# M66v2SCH.net
KiCad netlist of a schematic drawn in Altium Designer
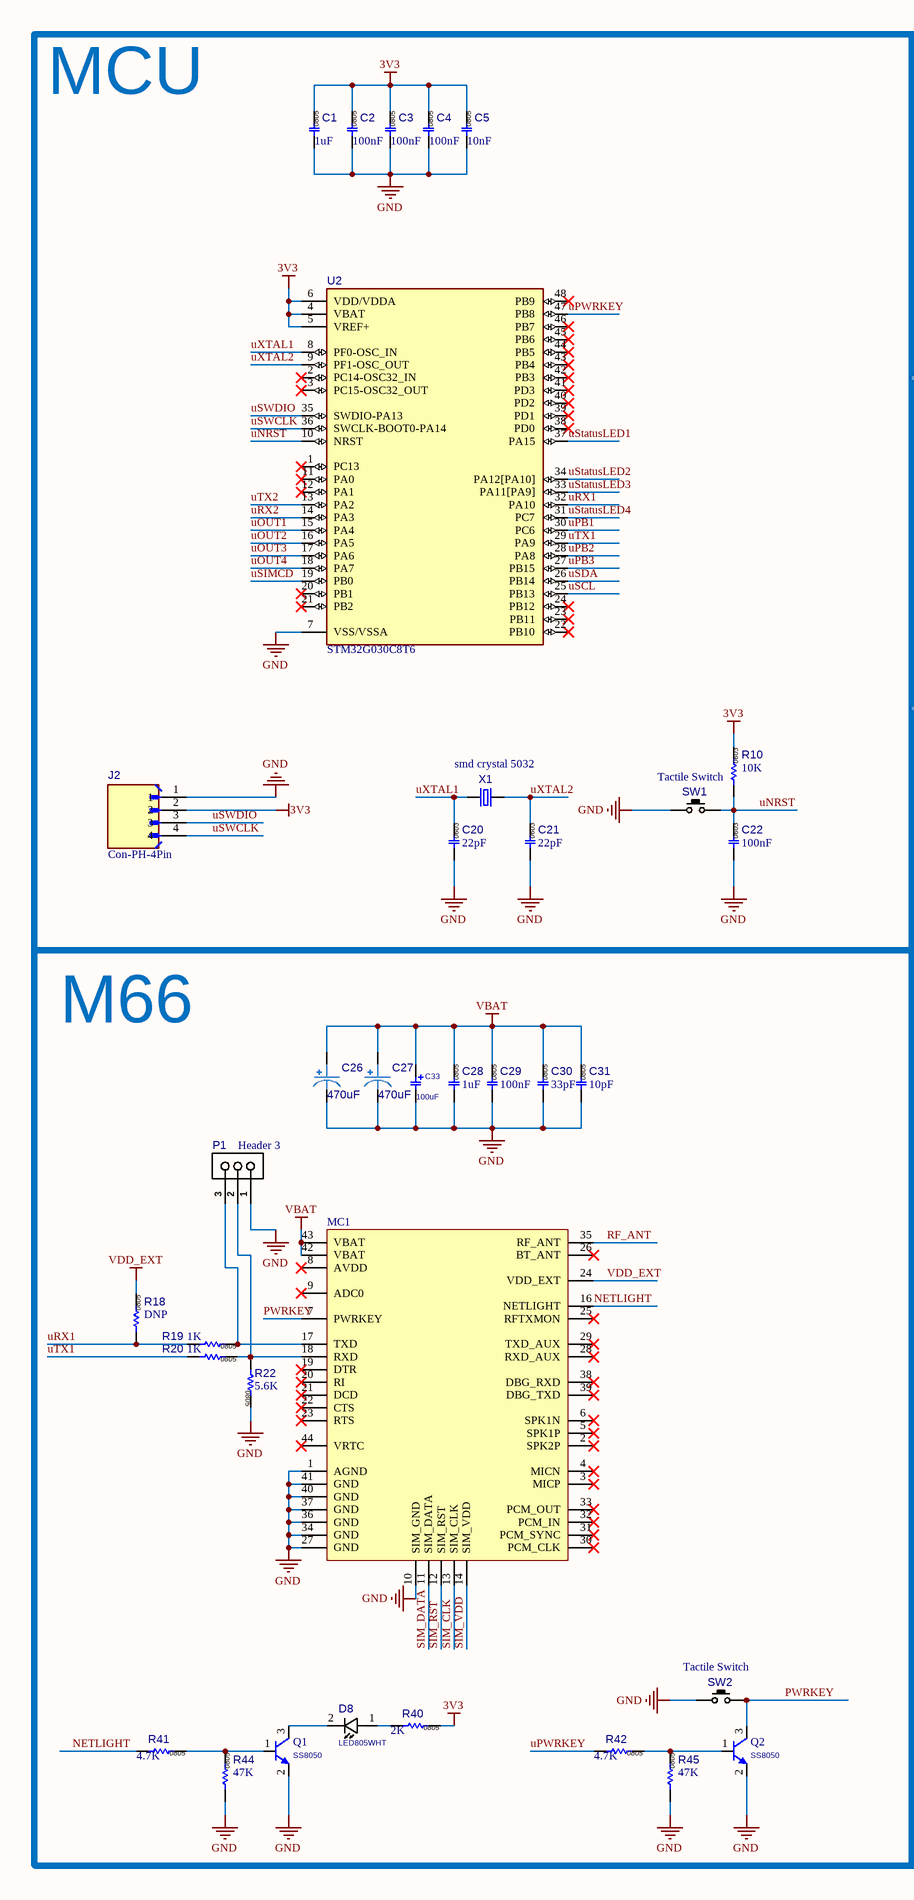
[diagram p0: M66v2SCH.SchDoc, left]
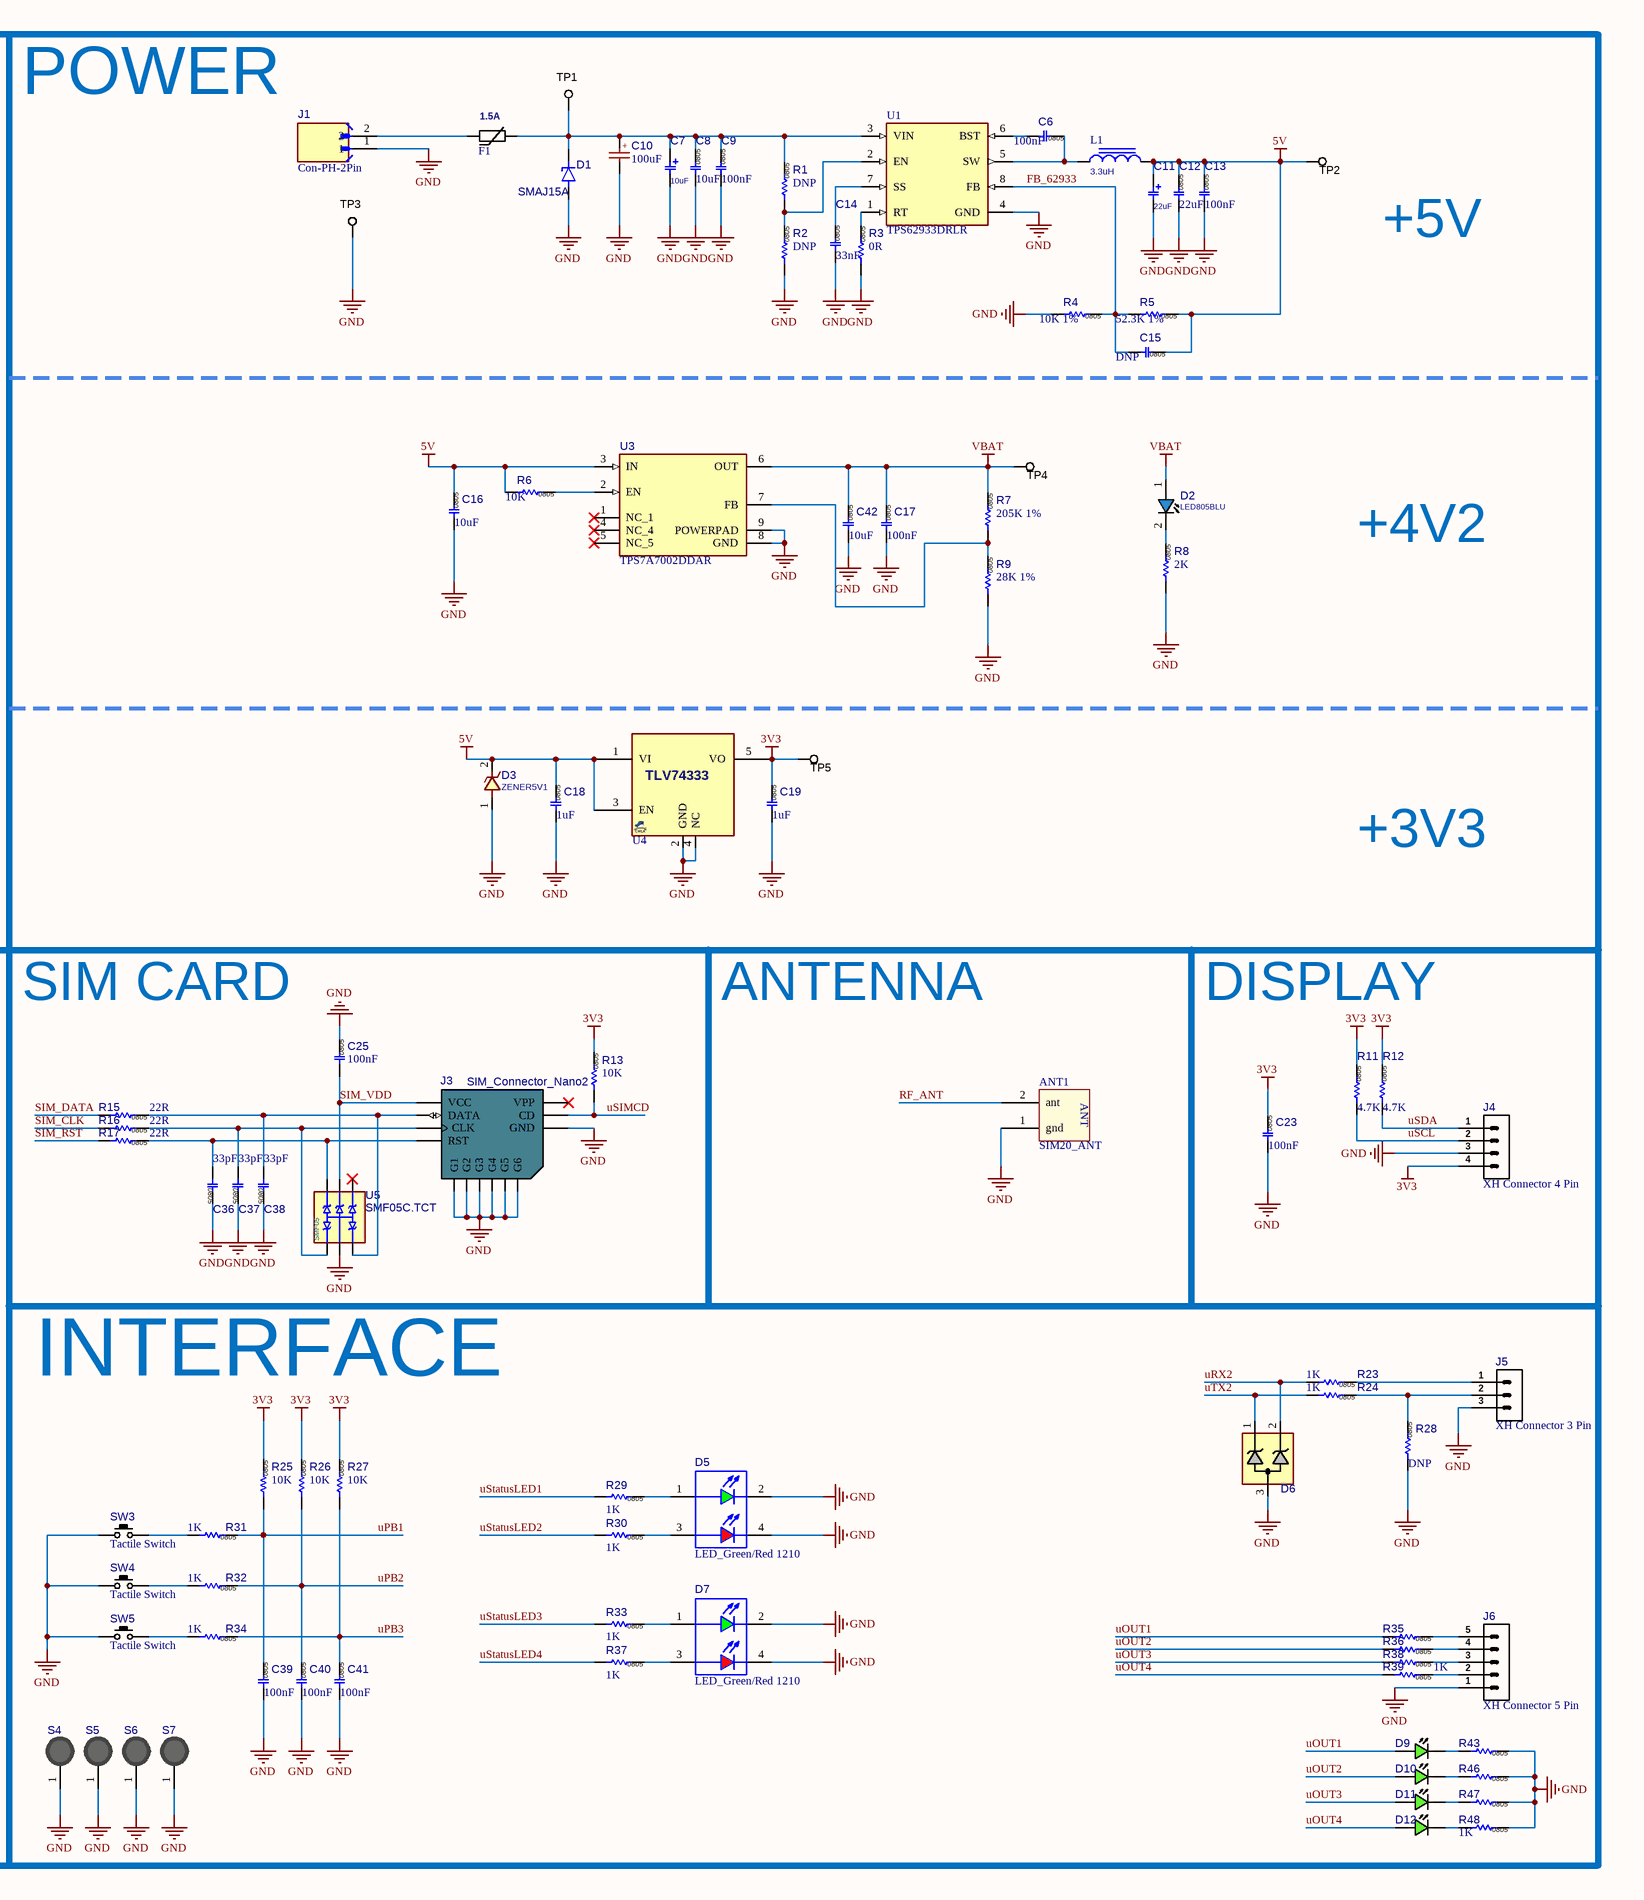
[diagram p1: M66v2SCH.SchDoc, right]

(export (version "E")
  (design (tool "Eeschema 10.0.6"))
  (components
    (comp (ref "ANT1")
      (value "SIM20_ANT")
      (footprint "MY_SIM20_ANT")
      (description "ANT")
      (libsource (lib "AMINLIB") (part "SIM20_ANT"))
    )
    (comp (ref "C1")
      (value "1uF")
      (footprint "Cap SMD 0805")
      (libsource (lib "Mehrdad") (part "Cap SMD 0805"))
    )
    (comp (ref "C2")
      (value "100nF")
      (footprint "Cap SMD 0805")
      (libsource (lib "Mehrdad") (part "Cap SMD 0805"))
    )
    (comp (ref "C3")
      (value "100nF")
      (footprint "Cap SMD 0805")
      (libsource (lib "Mehrdad") (part "Cap SMD 0805"))
    )
    (comp (ref "C4")
      (value "100nF")
      (footprint "Cap SMD 0805")
      (libsource (lib "Mehrdad") (part "Cap SMD 0805"))
    )
    (comp (ref "C5")
      (value "10nF")
      (footprint "Cap SMD 0805")
      (libsource (lib "Mehrdad") (part "Cap SMD 0805"))
    )
    (comp (ref "C6")
      (value "100nF")
      (footprint "Cap SMD 0805")
      (libsource (lib "Mehrdad") (part "Cap SMD 0805"))
    )
    (comp (ref "C7")
      (value "10uF")
      (footprint "C_TN_3216")
      (description "CAP, SMD, TAN,")
      (libsource (lib "passive_smd") (part "CAP_SMD_TAN_3216"))
    )
    (comp (ref "C8")
      (value "10uF")
      (footprint "Cap SMD 0805")
      (libsource (lib "Mehrdad") (part "Cap SMD 0805"))
    )
    (comp (ref "C9")
      (value "100nF")
      (footprint "Cap SMD 0805")
      (libsource (lib "Mehrdad") (part "Cap SMD 0805"))
    )
    (comp (ref "C10")
      (value "100uF")
      (footprint "Cap SMD 6.3x5.4mm")
      (description "SMD Aluminum Electrolytic Capacitor")
      (fields
        (field (name "VOLTAGE") "12v")
        (field (name "TOLERANCE") "5%")
        (field (name "PUBLISHER") "Majid Derhambakhsh")
      )
      (libsource (lib "mBedLab Altium Library (2024-04-20)") (part "CAP Electrolytic SMD"))
    )
    (comp (ref "C11")
      (value "22uF")
      (footprint "C_TN_3216")
      (description "CAP, SMD, TAN,")
      (libsource (lib "passive_smd") (part "CAP_SMD_TAN_3216"))
    )
    (comp (ref "C12")
      (value "22uF")
      (footprint "Cap SMD 0805")
      (libsource (lib "Mehrdad") (part "Cap SMD 0805"))
    )
    (comp (ref "C13")
      (value "100nF")
      (footprint "Cap SMD 0805")
      (libsource (lib "Mehrdad") (part "Cap SMD 0805"))
    )
    (comp (ref "C14")
      (value "33nF")
      (footprint "Cap SMD 0805")
      (libsource (lib "Mehrdad") (part "Cap SMD 0805"))
    )
    (comp (ref "C15")
      (value "DNP")
      (footprint "Cap SMD 0805")
      (libsource (lib "Mehrdad") (part "Cap SMD 0805"))
    )
    (comp (ref "C16")
      (value "10uF")
      (footprint "Cap SMD 0805")
      (libsource (lib "Mehrdad") (part "Cap SMD 0805"))
    )
    (comp (ref "C17")
      (value "100nF")
      (footprint "Cap SMD 0805")
      (libsource (lib "Mehrdad") (part "Cap SMD 0805"))
    )
    (comp (ref "C18")
      (value "1uF")
      (footprint "Cap SMD 0805")
      (libsource (lib "Mehrdad") (part "Cap SMD 0805"))
    )
    (comp (ref "C19")
      (value "1uF")
      (footprint "Cap SMD 0805")
      (libsource (lib "Mehrdad") (part "Cap SMD 0805"))
    )
    (comp (ref "C20")
      (value "22pF")
      (footprint "Cap SMD 0603")
      (libsource (lib "Mehrdad") (part "Cap SMD 0603"))
    )
    (comp (ref "C21")
      (value "22pF")
      (footprint "Cap SMD 0603")
      (libsource (lib "Mehrdad") (part "Cap SMD 0603"))
    )
    (comp (ref "C22")
      (value "100nF")
      (footprint "Cap SMD 0603")
      (libsource (lib "Mehrdad") (part "Cap SMD 0603"))
    )
    (comp (ref "C23")
      (value "100nF")
      (footprint "Cap SMD 0805")
      (libsource (lib "Mehrdad") (part "Cap SMD 0805"))
    )
    (comp (ref "C25")
      (value "100nF")
      (footprint "Cap SMD 0805")
      (libsource (lib "Mehrdad") (part "Cap SMD 0805"))
    )
    (comp (ref "C26")
      (value "470uF")
      (footprint "Solid Capacitor 6.3x8mm")
      (description "Solid Polymer Electrolytic Capacitor")
      (libsource (lib "Mehrdad") (part "CAP Solid"))
    )
    (comp (ref "C27")
      (value "470uF")
      (footprint "Solid Capacitor 6.3x8mm")
      (description "Solid Polymer Electrolytic Capacitor")
      (libsource (lib "Mehrdad") (part "CAP Solid"))
    )
    (comp (ref "C28")
      (value "1uF")
      (footprint "Cap SMD 0805")
      (libsource (lib "Mehrdad") (part "Cap SMD 0805"))
    )
    (comp (ref "C29")
      (value "100nF")
      (footprint "Cap SMD 0805")
      (libsource (lib "Mehrdad") (part "Cap SMD 0805"))
    )
    (comp (ref "C30")
      (value "33pF")
      (footprint "Cap SMD 0805")
      (libsource (lib "Mehrdad") (part "Cap SMD 0805"))
    )
    (comp (ref "C31")
      (value "10pF")
      (footprint "Cap SMD 0805")
      (libsource (lib "Mehrdad") (part "Cap SMD 0805"))
    )
    (comp (ref "C33")
      (value "100uF")
      (footprint "C_TN_3528_BLK")
      (description "CAP, SMD, TAN")
      (fields (field (name "MANF") "VISHAY") (field (name "MANF_P#") "T55A106M6R3C0300"))
      (libsource (lib "AVR_RCS") (part "CAP_SMD_TAN_4"))
    )
    (comp (ref "C36")
      (value "33pF")
      (footprint "Cap SMD 0805")
      (libsource (lib "Mehrdad") (part "Cap SMD 0805"))
    )
    (comp (ref "C37")
      (value "33pF")
      (footprint "Cap SMD 0805")
      (libsource (lib "Mehrdad") (part "Cap SMD 0805"))
    )
    (comp (ref "C38")
      (value "33pF")
      (footprint "Cap SMD 0805")
      (libsource (lib "Mehrdad") (part "Cap SMD 0805"))
    )
    (comp (ref "C39")
      (value "100nF")
      (footprint "Cap SMD 0805")
      (libsource (lib "Mehrdad") (part "Cap SMD 0805"))
    )
    (comp (ref "C40")
      (value "100nF")
      (footprint "Cap SMD 0805")
      (libsource (lib "Mehrdad") (part "Cap SMD 0805"))
    )
    (comp (ref "C41")
      (value "100nF")
      (footprint "Cap SMD 0805")
      (libsource (lib "Mehrdad") (part "Cap SMD 0805"))
    )
    (comp (ref "C42")
      (value "10uF")
      (footprint "Cap SMD 0805")
      (libsource (lib "Mehrdad") (part "Cap SMD 0805"))
    )
    (comp (ref "D1")
      (value "SMAJ15A")
      (footprint "SMAJ15A")
      (description "TVS Diode Uni-directional 15V SMA  BR Voltage : 16.7V  Clamping Volatage : 24.4V")
      (libsource (lib "Mehrdad") (part "SMAJ15A"))
    )
    (comp (ref "D2")
      (value "LED805BLU")
      (footprint "LED0805BLU")
      (description "LED, SMD, 0805, BLUE")
      (fields (field (name "MANF") "MANF") (field (name "MANF_P#") "MANF_PART#"))
      (libsource (lib "led(diode)") (part "LED_SMD_0805_BLU"))
    )
    (comp (ref "D3")
      (value "ZENER5V1")
      (footprint "D_SOD123W")
      (description "DIODE, ZENER, 1W, 5.1V")
      (fields (field (name "MANF") "Diodes") (field (name "MANF_P#") "BZT52HC5V1WF-7"))
      (libsource (lib "AVR_RCS") (part "DIODE_SMD_ZENER_BZT52HC5V1"))
    )
    (comp (ref "D5")
      (value "LED_Green/Red 1210")
      (footprint "LED_Green/Red 1210")
      (libsource (lib "Mehrdad") (part "LED_Green/Red 1210"))
    )
    (comp (ref "D6")
      (value "PESD3V3S2UT")
      (footprint "PESD3V3S2UT")
      (description "Uni-directional Double ESD Protection Diode. Working Voltage:3.3 , Breakdown Voltage:5.6")
      (libsource (lib "Mehrdad") (part "PESD3V3S2UT"))
    )
    (comp (ref "D7")
      (value "LED_Green/Red 1210")
      (footprint "LED_Green/Red 1210")
      (libsource (lib "Mehrdad") (part "LED_Green/Red 1210"))
    )
    (comp (ref "D8")
      (value "LED805WHT")
      (footprint "LED0805WHT")
      (description "LED, SMD, 0805, WHITE")
      (fields (field (name "MANF") "MANF") (field (name "MANF_P#") "MANF_PART#"))
      (libsource (lib "led(diode)") (part "LED_SMD_0805_WHT"))
    )
    (comp (ref "D9")
      (value "LED805GRN")
      (footprint "LED0805GRN")
      (description "LED, SMD, 0805, GREEN")
      (libsource (lib "led(diode)") (part "LED_SMD_0805_GRN"))
    )
    (comp (ref "D10")
      (value "LED805GRN")
      (footprint "LED0805GRN")
      (description "LED, SMD, 0805, GREEN")
      (libsource (lib "led(diode)") (part "LED_SMD_0805_GRN"))
    )
    (comp (ref "D11")
      (value "LED805GRN")
      (footprint "LED0805GRN")
      (description "LED, SMD, 0805, GREEN")
      (libsource (lib "led(diode)") (part "LED_SMD_0805_GRN"))
    )
    (comp (ref "D12")
      (value "LED805GRN")
      (footprint "LED0805GRN")
      (description "LED, SMD, 0805, GREEN")
      (libsource (lib "led(diode)") (part "LED_SMD_0805_GRN"))
    )
    (comp (ref "F1")
      (value "1.5A")
      (footprint "FUSE1206 (3216)")
      (fields (field (name "PUBLISHER") "Majid Derhambakhsh"))
      (libsource (lib "mBedLab Altium Library (2024-04-20)") (part "PPTC Resettable Fuses"))
    )
    (comp (ref "J1")
      (value "Con-PH-2Pin")
      (footprint "Con-PH-2Pin-ST")
      (description "Connector Header Through Hole 2 position 0.079 (2.00mm)")
      (libsource (lib "Mehrdad") (part "Con-PH-2Pin"))
    )
    (comp (ref "J2")
      (value "Con-PH-4Pin")
      (footprint "Con-PH-4Pin-ST")
      (description "Connector Header Through Hole 4 position 0.079 (2.00mm)")
      (libsource (lib "Mehrdad") (part "Con-PH-4Pin"))
    )
    (comp (ref "J3")
      (value "SIM_Connector_Nano2")
      (footprint "SIM_Connector_Nano2")
      (description "Nano Sim Card 6P SMT-Card Detection")
      (libsource (lib "Mehrdad") (part "SIM_Connector_Nano2"))
    )
    (comp (ref "J4")
      (value "XH Connector 4 Pin")
      (footprint "XH 4 Pin - 2.5mm")
      (description "XH, 4-Pin")
      (fields (field (name "PUBLISHER") "Majid Derhambakhsh"))
      (libsource (lib "mBedLab Altium Library (2024-04-20)") (part "XH 4"))
    )
    (comp (ref "J5")
      (value "XH Connector 3 Pin")
      (footprint "XH 3 Pin - 2.5mm")
      (description "XH, 3-Pin")
      (fields (field (name "PUBLISHER") "Majid Derhambakhsh"))
      (libsource (lib "mBedLab Altium Library (2024-04-20)") (part "XH 3"))
    )
    (comp (ref "J6")
      (value "XH Connector 5 Pin")
      (footprint "XH 5 Pin - 2.5mm")
      (description "XH, 5-Pin")
      (fields (field (name "PUBLISHER") "Majid Derhambakhsh"))
      (libsource (lib "mBedLab Altium Library (2024-04-20)") (part "XH 5"))
    )
    (comp (ref "L1")
      (value "3.3uH")
      (footprint "SMD Inductor 3")
      (description "1008 (2520 metric) Part Number : DFE252012F-4R7M=P2")
      (libsource (lib "Mehrdad") (part "SMD Inductor 3"))
    )
    (comp (ref "MC1")
      (value "M66")
      (footprint "m66")
      (description "Quectel GSM/GPRS Module")
      (fields (field (name "VALIDATION") "Valid"))
      (libsource (lib "AVR_RCS") (part "ModSen_Com_M66"))
    )
    (comp (ref "P1")
      (value "Header 3")
      (footprint "HDR 1X3 Male Top")
      (description "Header, 3-Pin")
      (fields (field (name "PUBLISHER") "Majid Derhambakhsh"))
      (libsource (lib "mBedLab Altium Library (2024-04-20)") (part "Header 3"))
    )
    (comp (ref "Q1")
      (value "SS8050")
      (footprint "SOT23_3")
      (description "BJT, NPN, 25v, 1.5A, SMD, SOT23")
      (fields (field (name "MANF") "GALAXY"))
      (libsource (lib "transistor_bjt") (part "NPN_SS8050_SOT23"))
    )
    (comp (ref "Q2")
      (value "SS8050")
      (footprint "SOT23_3")
      (description "BJT, NPN, 25v, 1.5A, SMD, SOT23")
      (fields (field (name "MANF") "GALAXY"))
      (libsource (lib "transistor_bjt") (part "NPN_SS8050_SOT23"))
    )
    (comp (ref "R1")
      (value "DNP")
      (footprint "Res SMD 0805")
      (libsource (lib "Mehrdad") (part "Res SMD 0805"))
    )
    (comp (ref "R2")
      (value "DNP")
      (footprint "Res SMD 0805")
      (libsource (lib "Mehrdad") (part "Res SMD 0805"))
    )
    (comp (ref "R3")
      (value "0R")
      (footprint "Res SMD 0805")
      (libsource (lib "Mehrdad") (part "Res SMD 0805"))
    )
    (comp (ref "R4")
      (value "10K 1%")
      (footprint "Res SMD 0805")
      (libsource (lib "Mehrdad") (part "Res SMD 0805"))
    )
    (comp (ref "R5")
      (value "52.3K 1%")
      (footprint "Res SMD 0805")
      (libsource (lib "Mehrdad") (part "Res SMD 0805"))
    )
    (comp (ref "R6")
      (value "10K")
      (footprint "Res SMD 0805")
      (libsource (lib "Mehrdad") (part "Res SMD 0805"))
    )
    (comp (ref "R7")
      (value "205K 1%")
      (footprint "Res SMD 0805")
      (libsource (lib "Mehrdad") (part "Res SMD 0805"))
    )
    (comp (ref "R8")
      (value "2K")
      (footprint "Res SMD 0805")
      (libsource (lib "Mehrdad") (part "Res SMD 0805"))
    )
    (comp (ref "R9")
      (value "28K 1%")
      (footprint "Res SMD 0805")
      (libsource (lib "Mehrdad") (part "Res SMD 0805"))
    )
    (comp (ref "R10")
      (value "10K")
      (footprint "Res SMD 0603")
      (libsource (lib "Mehrdad") (part "Res SMD 0603"))
    )
    (comp (ref "R11")
      (value "4.7K")
      (footprint "Res SMD 0805")
      (libsource (lib "Mehrdad") (part "Res SMD 0805"))
    )
    (comp (ref "R12")
      (value "4.7K")
      (footprint "Res SMD 0805")
      (libsource (lib "Mehrdad") (part "Res SMD 0805"))
    )
    (comp (ref "R13")
      (value "10K")
      (footprint "Res SMD 0805")
      (libsource (lib "Mehrdad") (part "Res SMD 0805"))
    )
    (comp (ref "R15")
      (value "22R")
      (footprint "Res SMD 0805")
      (libsource (lib "Mehrdad") (part "Res SMD 0805"))
    )
    (comp (ref "R16")
      (value "22R")
      (footprint "Res SMD 0805")
      (libsource (lib "Mehrdad") (part "Res SMD 0805"))
    )
    (comp (ref "R17")
      (value "22R")
      (footprint "Res SMD 0805")
      (libsource (lib "Mehrdad") (part "Res SMD 0805"))
    )
    (comp (ref "R18")
      (value "DNP")
      (footprint "Res SMD 0805")
      (libsource (lib "Mehrdad") (part "Res SMD 0805"))
    )
    (comp (ref "R19")
      (value "1K")
      (footprint "Res SMD 0805")
      (libsource (lib "Mehrdad") (part "Res SMD 0805"))
    )
    (comp (ref "R20")
      (value "1K")
      (footprint "Res SMD 0805")
      (libsource (lib "Mehrdad") (part "Res SMD 0805"))
    )
    (comp (ref "R22")
      (value "5.6K")
      (footprint "Res SMD 0805")
      (libsource (lib "Mehrdad") (part "Res SMD 0805"))
    )
    (comp (ref "R23")
      (value "1K")
      (footprint "Res SMD 0805")
      (libsource (lib "Mehrdad") (part "Res SMD 0805"))
    )
    (comp (ref "R24")
      (value "1K")
      (footprint "Res SMD 0805")
      (libsource (lib "Mehrdad") (part "Res SMD 0805"))
    )
    (comp (ref "R25")
      (value "10K")
      (footprint "Res SMD 0805")
      (libsource (lib "Mehrdad") (part "Res SMD 0805"))
    )
    (comp (ref "R26")
      (value "10K")
      (footprint "Res SMD 0805")
      (libsource (lib "Mehrdad") (part "Res SMD 0805"))
    )
    (comp (ref "R27")
      (value "10K")
      (footprint "Res SMD 0805")
      (libsource (lib "Mehrdad") (part "Res SMD 0805"))
    )
    (comp (ref "R28")
      (value "DNP")
      (footprint "Res SMD 0805")
      (libsource (lib "Mehrdad") (part "Res SMD 0805"))
    )
    (comp (ref "R29")
      (value "1K")
      (footprint "Res SMD 0805")
      (libsource (lib "Mehrdad") (part "Res SMD 0805"))
    )
    (comp (ref "R30")
      (value "1K")
      (footprint "Res SMD 0805")
      (libsource (lib "Mehrdad") (part "Res SMD 0805"))
    )
    (comp (ref "R31")
      (value "1K")
      (footprint "Res SMD 0805")
      (libsource (lib "Mehrdad") (part "Res SMD 0805"))
    )
    (comp (ref "R32")
      (value "1K")
      (footprint "Res SMD 0805")
      (libsource (lib "Mehrdad") (part "Res SMD 0805"))
    )
    (comp (ref "R33")
      (value "1K")
      (footprint "Res SMD 0805")
      (libsource (lib "Mehrdad") (part "Res SMD 0805"))
    )
    (comp (ref "R34")
      (value "1K")
      (footprint "Res SMD 0805")
      (libsource (lib "Mehrdad") (part "Res SMD 0805"))
    )
    (comp (ref "R35")
      (value "1K")
      (footprint "Res SMD 0805")
      (libsource (lib "Mehrdad") (part "Res SMD 0805"))
    )
    (comp (ref "R36")
      (value "1K")
      (footprint "Res SMD 0805")
      (libsource (lib "Mehrdad") (part "Res SMD 0805"))
    )
    (comp (ref "R37")
      (value "1K")
      (footprint "Res SMD 0805")
      (libsource (lib "Mehrdad") (part "Res SMD 0805"))
    )
    (comp (ref "R38")
      (value "1K")
      (footprint "Res SMD 0805")
      (libsource (lib "Mehrdad") (part "Res SMD 0805"))
    )
    (comp (ref "R39")
      (value "1K")
      (footprint "Res SMD 0805")
      (libsource (lib "Mehrdad") (part "Res SMD 0805"))
    )
    (comp (ref "R40")
      (value "2K")
      (footprint "Res SMD 0805")
      (libsource (lib "Mehrdad") (part "Res SMD 0805"))
    )
    (comp (ref "R41")
      (value "4.7K")
      (footprint "Res SMD 0805")
      (libsource (lib "Mehrdad") (part "Res SMD 0805"))
    )
    (comp (ref "R42")
      (value "4.7K")
      (footprint "Res SMD 0805")
      (libsource (lib "Mehrdad") (part "Res SMD 0805"))
    )
    (comp (ref "R43")
      (value "1K")
      (footprint "Res SMD 0805")
      (libsource (lib "Mehrdad") (part "Res SMD 0805"))
    )
    (comp (ref "R44")
      (value "47K")
      (footprint "Res SMD 0805")
      (libsource (lib "Mehrdad") (part "Res SMD 0805"))
    )
    (comp (ref "R45")
      (value "47K")
      (footprint "Res SMD 0805")
      (libsource (lib "Mehrdad") (part "Res SMD 0805"))
    )
    (comp (ref "R46")
      (value "1K")
      (footprint "Res SMD 0805")
      (libsource (lib "Mehrdad") (part "Res SMD 0805"))
    )
    (comp (ref "R47")
      (value "1K")
      (footprint "Res SMD 0805")
      (libsource (lib "Mehrdad") (part "Res SMD 0805"))
    )
    (comp (ref "R48")
      (value "1K")
      (footprint "Res SMD 0805")
      (libsource (lib "Mehrdad") (part "Res SMD 0805"))
    )
    (comp (ref "S4") (value "Screw 1") (footprint "Screw 1") (libsource (lib "Mehrdad") (part "Screw 1")))
    (comp (ref "S5") (value "Screw 1") (footprint "Screw 1") (libsource (lib "Mehrdad") (part "Screw 1")))
    (comp (ref "S6") (value "Screw 1") (footprint "Screw 1") (libsource (lib "Mehrdad") (part "Screw 1")))
    (comp (ref "S7") (value "Screw 1") (footprint "Screw 1") (libsource (lib "Mehrdad") (part "Screw 1")))
    (comp (ref "SW1")
      (value "Tactile Switch")
      (footprint "Tactil Switch 3*4*2")
      (description "3x6x5 mm - 2 Pin")
      (libsource (lib "Mehrdad") (part "Tactile Switch"))
    )
    (comp (ref "SW2")
      (value "Tactile Switch")
      (footprint "Tactile Switch 3*6*5")
      (libsource (lib "Mehrdad") (part "Tactile Switch"))
    )
    (comp (ref "SW3")
      (value "Tactile Switch")
      (footprint "Tactile Switch 6*6 - 2Pin")
      (libsource (lib "Mehrdad") (part "Tactile Switch"))
    )
    (comp (ref "SW4")
      (value "Tactile Switch")
      (footprint "Tactile Switch 6*6 - 2Pin")
      (libsource (lib "Mehrdad") (part "Tactile Switch"))
    )
    (comp (ref "SW5")
      (value "Tactile Switch")
      (footprint "Tactile Switch 6*6 - 2Pin")
      (libsource (lib "Mehrdad") (part "Tactile Switch"))
    )
    (comp (ref "TP1")
      (value "TESTPOINT_SMD")
      (footprint "TPSMD_S1")
      (description "TEST POINT")
      (fields (field (name "MANF") "MANF") (field (name "MANF_P#") "MANF_P#"))
      (libsource (lib "test-tp_jumper") (part "TESTPOINT_SMD"))
    )
    (comp (ref "TP2")
      (value "TESTPOINT_SMD")
      (footprint "TPSMD_S1")
      (description "TEST POINT")
      (fields (field (name "MANF") "MANF") (field (name "MANF_P#") "MANF_P#"))
      (libsource (lib "test-tp_jumper") (part "TESTPOINT_SMD"))
    )
    (comp (ref "TP3")
      (value "TESTPOINT_SMD")
      (footprint "TPSMD_S1")
      (description "TEST POINT")
      (fields (field (name "MANF") "MANF") (field (name "MANF_P#") "MANF_P#"))
      (libsource (lib "test-tp_jumper") (part "TESTPOINT_SMD"))
    )
    (comp (ref "TP4")
      (value "TESTPOINT_SMD")
      (footprint "TPSMD_S1")
      (description "TEST POINT")
      (fields (field (name "MANF") "MANF") (field (name "MANF_P#") "MANF_P#"))
      (libsource (lib "test-tp_jumper") (part "TESTPOINT_SMD"))
    )
    (comp (ref "TP5")
      (value "TESTPOINT_SMD")
      (footprint "TPSMD_S1")
      (description "TEST POINT")
      (fields (field (name "MANF") "MANF") (field (name "MANF_P#") "MANF_P#"))
      (libsource (lib "test-tp_jumper") (part "TESTPOINT_SMD"))
    )
    (comp (ref "U1")
      (value "TPS62933DRLR")
      (footprint "TPS62933DRLR")
      (description "3.8-V to 30-V, 3-A, 200-kHz to 2.2-MHz, low-IQ synchronous buck converter in SOT-583 package")
      (libsource (lib "Mehrdad") (part "TPS62933DRLR"))
    )
    (comp (ref "U2")
      (value "STM32G030C8T6")
      (footprint "STM32G030C8T6")
      (libsource (lib "Mehrdad") (part "STM32G030C8T6"))
    )
    (comp (ref "U3")
      (value "TPS7A7002DDAR")
      (footprint "TPS7A7002DDAR")
      (libsource (lib "Mehrdad") (part "TPS7A7002DDAR"))
    )
    (comp (ref "U4")
      (value "TLV74333")
      (footprint "SOT23_5")
      (description "REG, Linear, LDO0.12V, Fixed, 300mA, VIN1.4~5.5V, VOUT1~5.5V, SOT-23-5")
      (fields (field (name "MANF") "Texas Instruments") (field (name "MANF_P#") "TLV74333PDQN"))
      (libsource (lib "pwr_reg_linear_LDO_highPSRR") (part "VREG_TLV74333_SOT23"))
    )
    (comp (ref "U5")
      (value "SMF05C.TCT")
      (footprint "SMF05C.TCT")
      (description "12.5V Clamp 8A (8/20Âµs) Ipp Tvs Diode Surface Mount SC-88/SC70-6/SOT-363")
      (libsource (lib "Mehrdad") (part "SMF05C.TCT"))
    )
    (comp (ref "X1")
      (value "smd crystal 5032")
      (footprint "smd crystal 5032")
      (description "8Mhz - 2Pin - 5032 Package")
      (libsource (lib "Mehrdad") (part "smd crystal 5032"))
    )
  )
  (nets
    (net (code "1") (name "/FB_62933") (class "Default")
      (node (ref "C15") (pin "1") (pinfunction "1_1") (pintype "passive"))
      (node (ref "R4") (pin "2") (pinfunction "2_2") (pintype "passive"))
      (node (ref "R5") (pin "1") (pinfunction "1_1") (pintype "passive"))
      (node (ref "U1") (pin "8") (pinfunction "FB_8") (pintype "input"))
    )
    (net (code "2") (name "/NETLIGHT") (class "Default")
      (node (ref "MC1") (pin "16") (pinfunction "NETLIGHT_16") (pintype "passive"))
      (node (ref "R41") (pin "1") (pinfunction "1_1") (pintype "passive"))
    )
    (net (code "3") (name "/PWRKEY") (class "Default")
      (node (ref "MC1") (pin "7") (pinfunction "PWRKEY_7") (pintype "passive"))
      (node (ref "Q2") (pin "3") (pinfunction "C_3") (pintype "passive"))
      (node (ref "SW2") (pin "2") (pinfunction "P3_2") (pintype "passive"))
    )
    (net (code "4") (name "/RF_ANT") (class "Default")
      (node (ref "ANT1") (pin "2") (pinfunction "ant_2") (pintype "passive"))
      (node (ref "MC1") (pin "35") (pinfunction "RF_ANT_35") (pintype "passive"))
    )
    (net (code "5") (name "/SIM_CLK") (class "Default")
      (node (ref "MC1") (pin "13") (pinfunction "SIM_CLK_13") (pintype "passive"))
      (node (ref "R16") (pin "1") (pinfunction "1_1") (pintype "passive"))
    )
    (net (code "6") (name "/SIM_DATA") (class "Default")
      (node (ref "MC1") (pin "11") (pinfunction "SIM_DATA_11") (pintype "passive"))
      (node (ref "R15") (pin "1") (pinfunction "1_1") (pintype "passive"))
    )
    (net (code "7") (name "/SIM_RST") (class "Default")
      (node (ref "MC1") (pin "12") (pinfunction "SIM_RST_12") (pintype "passive"))
      (node (ref "R17") (pin "1") (pinfunction "1_1") (pintype "passive"))
    )
    (net (code "8") (name "/SIM_VDD") (class "Default")
      (node (ref "C25") (pin "1") (pinfunction "1_1") (pintype "passive"))
      (node (ref "J3") (pin "C1") (pinfunction "VCC_C1") (pintype "power_in"))
      (node (ref "MC1") (pin "14") (pinfunction "SIM_VDD_14") (pintype "passive"))
      (node (ref "U5") (pin "5") (pinfunction "C4_5") (pintype "passive"))
    )
    (net (code "9") (name "/uNRST") (class "Default")
      (node (ref "C22") (pin "2") (pinfunction "2_2") (pintype "passive"))
      (node (ref "R10") (pin "1") (pinfunction "1_1") (pintype "passive"))
      (node (ref "SW1") (pin "2") (pinfunction "P3_2") (pintype "passive"))
      (node (ref "U2") (pin "10") (pinfunction "NRST_10") (pintype "bidirectional"))
    )
    (net (code "10") (name "/uOUT1") (class "Default")
      (node (ref "D9") (pin "1") (pinfunction "ANODE_1") (pintype "passive"))
      (node (ref "R35") (pin "1") (pinfunction "1_1") (pintype "passive"))
      (node (ref "U2") (pin "15") (pinfunction "PA4_15") (pintype "bidirectional"))
    )
    (net (code "11") (name "/uOUT2") (class "Default")
      (node (ref "D10") (pin "1") (pinfunction "ANODE_1") (pintype "passive"))
      (node (ref "R36") (pin "1") (pinfunction "1_1") (pintype "passive"))
      (node (ref "U2") (pin "16") (pinfunction "PA5_16") (pintype "bidirectional"))
    )
    (net (code "12") (name "/uOUT3") (class "Default")
      (node (ref "D11") (pin "1") (pinfunction "ANODE_1") (pintype "passive"))
      (node (ref "R38") (pin "1") (pinfunction "1_1") (pintype "passive"))
      (node (ref "U2") (pin "17") (pinfunction "PA6_17") (pintype "bidirectional"))
    )
    (net (code "13") (name "/uOUT4") (class "Default")
      (node (ref "D12") (pin "1") (pinfunction "ANODE_1") (pintype "passive"))
      (node (ref "R39") (pin "1") (pinfunction "1_1") (pintype "passive"))
      (node (ref "U2") (pin "18") (pinfunction "PA7_18") (pintype "bidirectional"))
    )
    (net (code "14") (name "/uPB1") (class "Default")
      (node (ref "C39") (pin "2") (pinfunction "2_2") (pintype "passive"))
      (node (ref "R25") (pin "1") (pinfunction "1_1") (pintype "passive"))
      (node (ref "R31") (pin "2") (pinfunction "2_2") (pintype "passive"))
      (node (ref "U2") (pin "30") (pinfunction "PC6_30") (pintype "bidirectional"))
    )
    (net (code "15") (name "/uPB2") (class "Default")
      (node (ref "C40") (pin "2") (pinfunction "2_2") (pintype "passive"))
      (node (ref "R26") (pin "1") (pinfunction "1_1") (pintype "passive"))
      (node (ref "R32") (pin "2") (pinfunction "2_2") (pintype "passive"))
      (node (ref "U2") (pin "28") (pinfunction "PA8_28") (pintype "bidirectional"))
    )
    (net (code "16") (name "/uPB3") (class "Default")
      (node (ref "C41") (pin "2") (pinfunction "2_2") (pintype "passive"))
      (node (ref "R27") (pin "1") (pinfunction "1_1") (pintype "passive"))
      (node (ref "R34") (pin "2") (pinfunction "2_2") (pintype "passive"))
      (node (ref "U2") (pin "27") (pinfunction "PB15_27") (pintype "bidirectional"))
    )
    (net (code "17") (name "/uPWRKEY") (class "Default")
      (node (ref "R42") (pin "1") (pinfunction "1_1") (pintype "passive"))
      (node (ref "U2") (pin "47") (pinfunction "PB8_47") (pintype "bidirectional"))
    )
    (net (code "18") (name "/uRX1") (class "Default")
      (node (ref "R18") (pin "1") (pinfunction "1_1") (pintype "passive"))
      (node (ref "R19") (pin "1") (pinfunction "1_1") (pintype "passive"))
      (node (ref "U2") (pin "32") (pinfunction "PA10_32") (pintype "bidirectional"))
    )
    (net (code "19") (name "/uRX2") (class "Default")
      (node (ref "D6") (pin "2") (pinfunction "IO2_2") (pintype "passive"))
      (node (ref "R23") (pin "1") (pinfunction "1_1") (pintype "passive"))
      (node (ref "U2") (pin "14") (pinfunction "PA3_14") (pintype "bidirectional"))
    )
    (net (code "20") (name "/uSCL") (class "Default")
      (node (ref "J4") (pin "2") (pinfunction "2_2") (pintype "passive"))
      (node (ref "R11") (pin "1") (pinfunction "1_1") (pintype "passive"))
      (node (ref "U2") (pin "25") (pinfunction "PB13_25") (pintype "bidirectional"))
    )
    (net (code "21") (name "/uSDA") (class "Default")
      (node (ref "J4") (pin "1") (pinfunction "1_1") (pintype "passive"))
      (node (ref "R12") (pin "1") (pinfunction "1_1") (pintype "passive"))
      (node (ref "U2") (pin "26") (pinfunction "PB14_26") (pintype "bidirectional"))
    )
    (net (code "22") (name "/uSIMCD") (class "Default")
      (node (ref "J3") (pin "CD") (pinfunction "CD_CD") (pintype "open_collector"))
      (node (ref "R13") (pin "1") (pinfunction "1_1") (pintype "passive"))
      (node (ref "U2") (pin "19") (pinfunction "PB0_19") (pintype "bidirectional"))
    )
    (net (code "23") (name "/uSWCLK") (class "Default")
      (node (ref "J2") (pin "4") (pinfunction "4_4") (pintype "passive"))
      (node (ref "U2") (pin "36") (pinfunction "SWCLK-BOOT0-PA14_36") (pintype "bidirectional"))
    )
    (net (code "24") (name "/uSWDIO") (class "Default")
      (node (ref "J2") (pin "3") (pinfunction "3_3") (pintype "passive"))
      (node (ref "U2") (pin "35") (pinfunction "SWDIO-PA13_35") (pintype "bidirectional"))
    )
    (net (code "25") (name "/uStatusLED1") (class "Default")
      (node (ref "R29") (pin "1") (pinfunction "1_1") (pintype "passive"))
      (node (ref "U2") (pin "37") (pinfunction "PA15_37") (pintype "bidirectional"))
    )
    (net (code "26") (name "/uStatusLED2") (class "Default")
      (node (ref "R30") (pin "1") (pinfunction "1_1") (pintype "passive"))
      (node (ref "U2") (pin "34") (pinfunction "PA12[PA10]_34") (pintype "bidirectional"))
    )
    (net (code "27") (name "/uStatusLED3") (class "Default")
      (node (ref "R33") (pin "1") (pinfunction "1_1") (pintype "passive"))
      (node (ref "U2") (pin "33") (pinfunction "PA11[PA9]_33") (pintype "bidirectional"))
    )
    (net (code "28") (name "/uStatusLED4") (class "Default")
      (node (ref "R37") (pin "1") (pinfunction "1_1") (pintype "passive"))
      (node (ref "U2") (pin "31") (pinfunction "PC7_31") (pintype "bidirectional"))
    )
    (net (code "29") (name "/uTX1") (class "Default")
      (node (ref "R20") (pin "1") (pinfunction "1_1") (pintype "passive"))
      (node (ref "U2") (pin "29") (pinfunction "PA9_29") (pintype "bidirectional"))
    )
    (net (code "30") (name "/uTX2") (class "Default")
      (node (ref "D6") (pin "1") (pinfunction "IO1_1") (pintype "passive"))
      (node (ref "R24") (pin "1") (pinfunction "1_1") (pintype "passive"))
      (node (ref "U2") (pin "13") (pinfunction "PA2_13") (pintype "bidirectional"))
    )
    (net (code "31") (name "/uXTAL1") (class "Default")
      (node (ref "C20") (pin "2") (pinfunction "2_2") (pintype "passive"))
      (node (ref "U2") (pin "8") (pinfunction "PF0-OSC_IN_8") (pintype "bidirectional"))
      (node (ref "X1") (pin "1") (pinfunction "1_1") (pintype "passive"))
    )
    (net (code "32") (name "/uXTAL2") (class "Default")
      (node (ref "C21") (pin "2") (pinfunction "2_2") (pintype "passive"))
      (node (ref "U2") (pin "9") (pinfunction "PF1-OSC_OUT_9") (pintype "bidirectional"))
      (node (ref "X1") (pin "2") (pinfunction "2_2") (pintype "passive"))
    )
    (net (code "33") (name "3V3") (class "Default")
      (node (ref "C1") (pin "2") (pinfunction "2_2") (pintype "passive"))
      (node (ref "C19") (pin "2") (pinfunction "2_2") (pintype "passive"))
      (node (ref "C2") (pin "2") (pinfunction "2_2") (pintype "passive"))
      (node (ref "C23") (pin "2") (pinfunction "2_2") (pintype "passive"))
      (node (ref "C3") (pin "2") (pinfunction "2_2") (pintype "passive"))
      (node (ref "C4") (pin "2") (pinfunction "2_2") (pintype "passive"))
      (node (ref "C5") (pin "2") (pinfunction "2_2") (pintype "passive"))
      (node (ref "J2") (pin "2") (pinfunction "2_2") (pintype "passive"))
      (node (ref "J4") (pin "4") (pinfunction "4_4") (pintype "passive"))
      (node (ref "R10") (pin "2") (pinfunction "2_2") (pintype "passive"))
      (node (ref "R11") (pin "2") (pinfunction "2_2") (pintype "passive"))
      (node (ref "R12") (pin "2") (pinfunction "2_2") (pintype "passive"))
      (node (ref "R13") (pin "2") (pinfunction "2_2") (pintype "passive"))
      (node (ref "R25") (pin "2") (pinfunction "2_2") (pintype "passive"))
      (node (ref "R26") (pin "2") (pinfunction "2_2") (pintype "passive"))
      (node (ref "R27") (pin "2") (pinfunction "2_2") (pintype "passive"))
      (node (ref "R40") (pin "2") (pinfunction "2_2") (pintype "passive"))
      (node (ref "TP5") (pin "1") (pinfunction "1_1") (pintype "passive"))
      (node (ref "U2") (pin "4") (pinfunction "VBAT_4") (pintype "power_in"))
      (node (ref "U2") (pin "5") (pinfunction "VREF+_5") (pintype "power_in"))
      (node (ref "U2") (pin "6") (pinfunction "VDD/VDDA_6") (pintype "power_in"))
      (node (ref "U4") (pin "5") (pinfunction "VO_5") (pintype "passive"))
    )
    (net (code "34") (name "5V") (class "Default")
      (node (ref "C11") (pin "1") (pinfunction "1_1") (pintype "passive"))
      (node (ref "C12") (pin "2") (pinfunction "2_2") (pintype "passive"))
      (node (ref "C13") (pin "2") (pinfunction "2_2") (pintype "passive"))
      (node (ref "C15") (pin "2") (pinfunction "2_2") (pintype "passive"))
      (node (ref "C16") (pin "2") (pinfunction "2_2") (pintype "passive"))
      (node (ref "C18") (pin "2") (pinfunction "2_2") (pintype "passive"))
      (node (ref "D3") (pin "2") (pinfunction "2_2") (pintype "passive"))
      (node (ref "L1") (pin "2") (pinfunction "2_2") (pintype "passive"))
      (node (ref "R5") (pin "2") (pinfunction "2_2") (pintype "passive"))
      (node (ref "R6") (pin "1") (pinfunction "1_1") (pintype "passive"))
      (node (ref "TP2") (pin "1") (pinfunction "1_1") (pintype "passive"))
      (node (ref "U3") (pin "3") (pinfunction "IN_3") (pintype "input"))
      (node (ref "U4") (pin "1") (pinfunction "VI_1") (pintype "passive"))
      (node (ref "U4") (pin "3") (pinfunction "EN_3") (pintype "passive"))
    )
    (net (code "35") (name "GND") (class "Default")
      (node (ref "ANT1") (pin "1") (pinfunction "gnd_1") (pintype "passive"))
      (node (ref "C1") (pin "1") (pinfunction "1_1") (pintype "passive"))
      (node (ref "C10") (pin "2") (pinfunction "-_2") (pintype "passive"))
      (node (ref "C11") (pin "2") (pinfunction "2_2") (pintype "passive"))
      (node (ref "C12") (pin "1") (pinfunction "1_1") (pintype "passive"))
      (node (ref "C13") (pin "1") (pinfunction "1_1") (pintype "passive"))
      (node (ref "C14") (pin "1") (pinfunction "1_1") (pintype "passive"))
      (node (ref "C16") (pin "1") (pinfunction "1_1") (pintype "passive"))
      (node (ref "C17") (pin "1") (pinfunction "1_1") (pintype "passive"))
      (node (ref "C18") (pin "1") (pinfunction "1_1") (pintype "passive"))
      (node (ref "C19") (pin "1") (pinfunction "1_1") (pintype "passive"))
      (node (ref "C2") (pin "1") (pinfunction "1_1") (pintype "passive"))
      (node (ref "C20") (pin "1") (pinfunction "1_1") (pintype "passive"))
      (node (ref "C21") (pin "1") (pinfunction "1_1") (pintype "passive"))
      (node (ref "C22") (pin "1") (pinfunction "1_1") (pintype "passive"))
      (node (ref "C23") (pin "1") (pinfunction "1_1") (pintype "passive"))
      (node (ref "C25") (pin "2") (pinfunction "2_2") (pintype "passive"))
      (node (ref "C26") (pin "2") (pinfunction "N_2") (pintype "passive"))
      (node (ref "C27") (pin "2") (pinfunction "N_2") (pintype "passive"))
      (node (ref "C28") (pin "1") (pinfunction "1_1") (pintype "passive"))
      (node (ref "C29") (pin "1") (pinfunction "1_1") (pintype "passive"))
      (node (ref "C3") (pin "1") (pinfunction "1_1") (pintype "passive"))
      (node (ref "C30") (pin "1") (pinfunction "1_1") (pintype "passive"))
      (node (ref "C31") (pin "1") (pinfunction "1_1") (pintype "passive"))
      (node (ref "C33") (pin "2") (pinfunction "2_2") (pintype "passive"))
      (node (ref "C36") (pin "2") (pinfunction "2_2") (pintype "passive"))
      (node (ref "C37") (pin "2") (pinfunction "2_2") (pintype "passive"))
      (node (ref "C38") (pin "2") (pinfunction "2_2") (pintype "passive"))
      (node (ref "C39") (pin "1") (pinfunction "1_1") (pintype "passive"))
      (node (ref "C4") (pin "1") (pinfunction "1_1") (pintype "passive"))
      (node (ref "C40") (pin "1") (pinfunction "1_1") (pintype "passive"))
      (node (ref "C41") (pin "1") (pinfunction "1_1") (pintype "passive"))
      (node (ref "C42") (pin "1") (pinfunction "1_1") (pintype "passive"))
      (node (ref "C5") (pin "1") (pinfunction "1_1") (pintype "passive"))
      (node (ref "C7") (pin "2") (pinfunction "2_2") (pintype "passive"))
      (node (ref "C8") (pin "1") (pinfunction "1_1") (pintype "passive"))
      (node (ref "C9") (pin "1") (pinfunction "1_1") (pintype "passive"))
      (node (ref "D1") (pin "A") (pinfunction "A_A") (pintype "passive"))
      (node (ref "D3") (pin "1") (pinfunction "1_1") (pintype "passive"))
      (node (ref "D5") (pin "2") (pinfunction "RED_K_2") (pintype "passive"))
      (node (ref "D5") (pin "4") (pinfunction "BLUE_K_4") (pintype "passive"))
      (node (ref "D6") (pin "3") (pinfunction "GND_3") (pintype "passive"))
      (node (ref "D7") (pin "2") (pinfunction "RED_K_2") (pintype "passive"))
      (node (ref "D7") (pin "4") (pinfunction "BLUE_K_4") (pintype "passive"))
      (node (ref "J1") (pin "1") (pinfunction "1_1") (pintype "passive"))
      (node (ref "J2") (pin "1") (pinfunction "1_1") (pintype "passive"))
      (node (ref "J3") (pin "C5") (pinfunction "GND_C5") (pintype "power_in"))
      (node (ref "J3") (pin "G1") (pinfunction "G1_G1") (pintype "power_in"))
      (node (ref "J3") (pin "G2") (pinfunction "G2_G2") (pintype "power_in"))
      (node (ref "J3") (pin "G3") (pinfunction "G3_G3") (pintype "power_in"))
      (node (ref "J3") (pin "G4") (pinfunction "G4_G4") (pintype "power_in"))
      (node (ref "J3") (pin "G5") (pinfunction "G5_G5") (pintype "power_in"))
      (node (ref "J3") (pin "G6") (pinfunction "G6_G6") (pintype "power_in"))
      (node (ref "J4") (pin "3") (pinfunction "3_3") (pintype "passive"))
      (node (ref "J5") (pin "3") (pinfunction "3_3") (pintype "passive"))
      (node (ref "J6") (pin "1") (pinfunction "1_1") (pintype "passive"))
      (node (ref "MC1") (pin "1") (pinfunction "AGND_1") (pintype "passive"))
      (node (ref "MC1") (pin "10") (pinfunction "SIM_GND_10") (pintype "passive"))
      (node (ref "MC1") (pin "27") (pinfunction "GND_27") (pintype "passive"))
      (node (ref "MC1") (pin "34") (pinfunction "GND_34") (pintype "passive"))
      (node (ref "MC1") (pin "36") (pinfunction "GND_36") (pintype "passive"))
      (node (ref "MC1") (pin "37") (pinfunction "GND_37") (pintype "passive"))
      (node (ref "MC1") (pin "40") (pinfunction "GND_40") (pintype "passive"))
      (node (ref "MC1") (pin "41") (pinfunction "GND_41") (pintype "passive"))
      (node (ref "P1") (pin "1") (pinfunction "1_1") (pintype "passive"))
      (node (ref "Q1") (pin "2") (pinfunction "E_2") (pintype "passive"))
      (node (ref "Q2") (pin "2") (pinfunction "E_2") (pintype "passive"))
      (node (ref "R2") (pin "1") (pinfunction "1_1") (pintype "passive"))
      (node (ref "R22") (pin "2") (pinfunction "2_2") (pintype "passive"))
      (node (ref "R28") (pin "1") (pinfunction "1_1") (pintype "passive"))
      (node (ref "R3") (pin "1") (pinfunction "1_1") (pintype "passive"))
      (node (ref "R4") (pin "1") (pinfunction "1_1") (pintype "passive"))
      (node (ref "R43") (pin "2") (pinfunction "2_2") (pintype "passive"))
      (node (ref "R44") (pin "1") (pinfunction "1_1") (pintype "passive"))
      (node (ref "R45") (pin "1") (pinfunction "1_1") (pintype "passive"))
      (node (ref "R46") (pin "2") (pinfunction "2_2") (pintype "passive"))
      (node (ref "R47") (pin "2") (pinfunction "2_2") (pintype "passive"))
      (node (ref "R48") (pin "2") (pinfunction "2_2") (pintype "passive"))
      (node (ref "R8") (pin "1") (pinfunction "1_1") (pintype "passive"))
      (node (ref "R9") (pin "1") (pinfunction "1_1") (pintype "passive"))
      (node (ref "S4") (pin "1") (pinfunction "1_1") (pintype "power_in"))
      (node (ref "S5") (pin "1") (pinfunction "1_1") (pintype "power_in"))
      (node (ref "S6") (pin "1") (pinfunction "1_1") (pintype "power_in"))
      (node (ref "S7") (pin "1") (pinfunction "1_1") (pintype "power_in"))
      (node (ref "SW1") (pin "1") (pinfunction "P1_1") (pintype "passive"))
      (node (ref "SW2") (pin "1") (pinfunction "P1_1") (pintype "passive"))
      (node (ref "SW3") (pin "1") (pinfunction "P1_1") (pintype "passive"))
      (node (ref "SW4") (pin "1") (pinfunction "P1_1") (pintype "passive"))
      (node (ref "SW5") (pin "1") (pinfunction "P1_1") (pintype "passive"))
      (node (ref "TP3") (pin "1") (pinfunction "1_1") (pintype "passive"))
      (node (ref "U1") (pin "4") (pinfunction "GND_4") (pintype "power_in"))
      (node (ref "U2") (pin "7") (pinfunction "VSS/VSSA_7") (pintype "power_in"))
      (node (ref "U3") (pin "8") (pinfunction "GND_8") (pintype "power_in"))
      (node (ref "U3") (pin "9") (pinfunction "POWERPAD_9") (pintype "power_in"))
      (node (ref "U4") (pin "2") (pinfunction "GND_2") (pintype "passive"))
      (node (ref "U4") (pin "4") (pinfunction "NC_4") (pintype "passive"))
      (node (ref "U5") (pin "2") (pinfunction "A_2") (pintype "passive"))
    )
    (net (code "36") (name "Net-(C10-+)") (class "Default")
      (node (ref "C10") (pin "1") (pinfunction "+_1") (pintype "passive"))
      (node (ref "C7") (pin "1") (pinfunction "1_1") (pintype "passive"))
      (node (ref "C8") (pin "2") (pinfunction "2_2") (pintype "passive"))
      (node (ref "C9") (pin "2") (pinfunction "2_2") (pintype "passive"))
      (node (ref "D1") (pin "C") (pinfunction "C_C") (pintype "passive"))
      (node (ref "F1") (pin "2") (pinfunction "2_2") (pintype "passive"))
      (node (ref "R1") (pin "2") (pinfunction "2_2") (pintype "passive"))
      (node (ref "TP1") (pin "1") (pinfunction "1_1") (pintype "passive"))
      (node (ref "U1") (pin "3") (pinfunction "VIN_3") (pintype "input"))
    )
    (net (code "37") (name "Net-(D2-CATHODE)") (class "Default")
      (node (ref "D2") (pin "2") (pinfunction "CATHODE_2") (pintype "passive"))
      (node (ref "R8") (pin "2") (pinfunction "2_2") (pintype "passive"))
    )
    (net (code "38") (name "Net-(D5-A)") (class "Default")
      (node (ref "D5") (pin "1") (pinfunction "A_1") (pintype "passive"))
      (node (ref "R29") (pin "2") (pinfunction "2_2") (pintype "passive"))
    )
    (net (code "39") (name "Net-(D5-GREEN_K)") (class "Default")
      (node (ref "D5") (pin "3") (pinfunction "GREEN_K_3") (pintype "passive"))
      (node (ref "R30") (pin "2") (pinfunction "2_2") (pintype "passive"))
    )
    (net (code "40") (name "Net-(D7-A)") (class "Default")
      (node (ref "D7") (pin "1") (pinfunction "A_1") (pintype "passive"))
      (node (ref "R33") (pin "2") (pinfunction "2_2") (pintype "passive"))
    )
    (net (code "41") (name "Net-(D7-GREEN_K)") (class "Default")
      (node (ref "D7") (pin "3") (pinfunction "GREEN_K_3") (pintype "passive"))
      (node (ref "R37") (pin "2") (pinfunction "2_2") (pintype "passive"))
    )
    (net (code "42") (name "Net-(D8-ANODE)") (class "Default")
      (node (ref "D8") (pin "1") (pinfunction "ANODE_1") (pintype "passive"))
      (node (ref "R40") (pin "1") (pinfunction "1_1") (pintype "passive"))
    )
    (net (code "43") (name "Net-(D8-CATHODE)") (class "Default")
      (node (ref "D8") (pin "2") (pinfunction "CATHODE_2") (pintype "passive"))
      (node (ref "Q1") (pin "3") (pinfunction "C_3") (pintype "passive"))
    )
    (net (code "44") (name "Net-(D9-CATHODE)") (class "Default")
      (node (ref "D9") (pin "2") (pinfunction "CATHODE_2") (pintype "passive"))
      (node (ref "R43") (pin "1") (pinfunction "1_1") (pintype "passive"))
    )
    (net (code "45") (name "Net-(D10-CATHODE)") (class "Default")
      (node (ref "D10") (pin "2") (pinfunction "CATHODE_2") (pintype "passive"))
      (node (ref "R46") (pin "1") (pinfunction "1_1") (pintype "passive"))
    )
    (net (code "46") (name "Net-(D11-CATHODE)") (class "Default")
      (node (ref "D11") (pin "2") (pinfunction "CATHODE_2") (pintype "passive"))
      (node (ref "R47") (pin "1") (pinfunction "1_1") (pintype "passive"))
    )
    (net (code "47") (name "Net-(D12-CATHODE)") (class "Default")
      (node (ref "D12") (pin "2") (pinfunction "CATHODE_2") (pintype "passive"))
      (node (ref "R48") (pin "1") (pinfunction "1_1") (pintype "passive"))
    )
    (net (code "48") (name "Net-(F1-Pad1)") (class "Default")
      (node (ref "F1") (pin "1") (pinfunction "1_1") (pintype "passive"))
      (node (ref "J1") (pin "2") (pinfunction "2_2") (pintype "passive"))
    )
    (net (code "49") (name "Net-(J3-CLK)") (class "Default")
      (node (ref "C37") (pin "1") (pinfunction "1_1") (pintype "passive"))
      (node (ref "J3") (pin "C3") (pinfunction "CLK_C3") (pintype "passive"))
      (node (ref "R16") (pin "2") (pinfunction "2_2") (pintype "passive"))
      (node (ref "U5") (pin "1") (pinfunction "C1_1") (pintype "passive"))
    )
    (net (code "50") (name "Net-(J3-DATA)") (class "Default")
      (node (ref "C38") (pin "1") (pinfunction "1_1") (pintype "passive"))
      (node (ref "J3") (pin "C7") (pinfunction "DATA_C7") (pintype "bidirectional"))
      (node (ref "R15") (pin "2") (pinfunction "2_2") (pintype "passive"))
      (node (ref "U5") (pin "3") (pinfunction "C2_3") (pintype "passive"))
    )
    (net (code "51") (name "Net-(J3-RST)") (class "Default")
      (node (ref "C36") (pin "1") (pinfunction "1_1") (pintype "passive"))
      (node (ref "J3") (pin "C2") (pinfunction "RST_C2") (pintype "passive"))
      (node (ref "R17") (pin "2") (pinfunction "2_2") (pintype "passive"))
      (node (ref "U5") (pin "6") (pinfunction "C5_6") (pintype "passive"))
    )
    (net (code "52") (name "Net-(J5-Pad1)") (class "Default")
      (node (ref "J5") (pin "1") (pinfunction "1_1") (pintype "passive"))
      (node (ref "R23") (pin "2") (pinfunction "2_2") (pintype "passive"))
    )
    (net (code "53") (name "Net-(J5-Pad2)") (class "Default")
      (node (ref "J5") (pin "2") (pinfunction "2_2") (pintype "passive"))
      (node (ref "R24") (pin "2") (pinfunction "2_2") (pintype "passive"))
      (node (ref "R28") (pin "2") (pinfunction "2_2") (pintype "passive"))
    )
    (net (code "54") (name "Net-(J6-Pad2)") (class "Default")
      (node (ref "J6") (pin "2") (pinfunction "2_2") (pintype "passive"))
      (node (ref "R39") (pin "2") (pinfunction "2_2") (pintype "passive"))
    )
    (net (code "55") (name "Net-(J6-Pad3)") (class "Default")
      (node (ref "J6") (pin "3") (pinfunction "3_3") (pintype "passive"))
      (node (ref "R38") (pin "2") (pinfunction "2_2") (pintype "passive"))
    )
    (net (code "56") (name "Net-(J6-Pad4)") (class "Default")
      (node (ref "J6") (pin "4") (pinfunction "4_4") (pintype "passive"))
      (node (ref "R36") (pin "2") (pinfunction "2_2") (pintype "passive"))
    )
    (net (code "57") (name "Net-(J6-Pad5)") (class "Default")
      (node (ref "J6") (pin "5") (pinfunction "5_5") (pintype "passive"))
      (node (ref "R35") (pin "2") (pinfunction "2_2") (pintype "passive"))
    )
    (net (code "58") (name "Net-(MC1-RXD)") (class "Default")
      (node (ref "MC1") (pin "18") (pinfunction "RXD_18") (pintype "passive"))
      (node (ref "P1") (pin "2") (pinfunction "2_2") (pintype "passive"))
      (node (ref "R20") (pin "2") (pinfunction "2_2") (pintype "passive"))
      (node (ref "R22") (pin "1") (pinfunction "1_1") (pintype "passive"))
    )
    (net (code "59") (name "Net-(MC1-TXD)") (class "Default")
      (node (ref "MC1") (pin "17") (pinfunction "TXD_17") (pintype "passive"))
      (node (ref "P1") (pin "3") (pinfunction "3_3") (pintype "passive"))
      (node (ref "R19") (pin "2") (pinfunction "2_2") (pintype "passive"))
    )
    (net (code "60") (name "Net-(Q1-B)") (class "Default")
      (node (ref "Q1") (pin "1") (pinfunction "B_1") (pintype "passive"))
      (node (ref "R41") (pin "2") (pinfunction "2_2") (pintype "passive"))
      (node (ref "R44") (pin "2") (pinfunction "2_2") (pintype "passive"))
    )
    (net (code "61") (name "Net-(Q2-B)") (class "Default")
      (node (ref "Q2") (pin "1") (pinfunction "B_1") (pintype "passive"))
      (node (ref "R42") (pin "2") (pinfunction "2_2") (pintype "passive"))
      (node (ref "R45") (pin "2") (pinfunction "2_2") (pintype "passive"))
    )
    (net (code "62") (name "Net-(SW3-P3)") (class "Default")
      (node (ref "R31") (pin "1") (pinfunction "1_1") (pintype "passive"))
      (node (ref "SW3") (pin "2") (pinfunction "P3_2") (pintype "passive"))
    )
    (net (code "63") (name "Net-(SW4-P3)") (class "Default")
      (node (ref "R32") (pin "1") (pinfunction "1_1") (pintype "passive"))
      (node (ref "SW4") (pin "2") (pinfunction "P3_2") (pintype "passive"))
    )
    (net (code "64") (name "Net-(SW5-P3)") (class "Default")
      (node (ref "R34") (pin "1") (pinfunction "1_1") (pintype "passive"))
      (node (ref "SW5") (pin "2") (pinfunction "P3_2") (pintype "passive"))
    )
    (net (code "65") (name "Net-(U1-BST)") (class "Default")
      (node (ref "C6") (pin "1") (pinfunction "1_1") (pintype "passive"))
      (node (ref "U1") (pin "6") (pinfunction "BST_6") (pintype "input"))
    )
    (net (code "66") (name "Net-(U1-EN)") (class "Default")
      (node (ref "R1") (pin "1") (pinfunction "1_1") (pintype "passive"))
      (node (ref "R2") (pin "2") (pinfunction "2_2") (pintype "passive"))
      (node (ref "U1") (pin "2") (pinfunction "EN_2") (pintype "input"))
    )
    (net (code "67") (name "Net-(U1-RT)") (class "Default")
      (node (ref "R3") (pin "2") (pinfunction "2_2") (pintype "passive"))
      (node (ref "U1") (pin "1") (pinfunction "RT_1") (pintype "input"))
    )
    (net (code "68") (name "Net-(U1-SS)") (class "Default")
      (node (ref "C14") (pin "2") (pinfunction "2_2") (pintype "passive"))
      (node (ref "U1") (pin "7") (pinfunction "SS_7") (pintype "input"))
    )
    (net (code "69") (name "Net-(U1-SW)") (class "Default")
      (node (ref "C6") (pin "2") (pinfunction "2_2") (pintype "passive"))
      (node (ref "L1") (pin "1") (pinfunction "1_1") (pintype "passive"))
      (node (ref "U1") (pin "5") (pinfunction "SW_5") (pintype "output"))
    )
    (net (code "70") (name "Net-(U3-EN)") (class "Default")
      (node (ref "R6") (pin "2") (pinfunction "2_2") (pintype "passive"))
      (node (ref "U3") (pin "2") (pinfunction "EN_2") (pintype "input"))
    )
    (net (code "71") (name "Net-(U3-FB)") (class "Default")
      (node (ref "R7") (pin "1") (pinfunction "1_1") (pintype "passive"))
      (node (ref "R9") (pin "2") (pinfunction "2_2") (pintype "passive"))
      (node (ref "U3") (pin "7") (pinfunction "FB_7") (pintype "passive"))
    )
    (net (code "72") (name "VBAT") (class "Default")
      (node (ref "C17") (pin "2") (pinfunction "2_2") (pintype "passive"))
      (node (ref "C26") (pin "1") (pinfunction "P_1") (pintype "power_in"))
      (node (ref "C27") (pin "1") (pinfunction "P_1") (pintype "power_in"))
      (node (ref "C28") (pin "2") (pinfunction "2_2") (pintype "passive"))
      (node (ref "C29") (pin "2") (pinfunction "2_2") (pintype "passive"))
      (node (ref "C30") (pin "2") (pinfunction "2_2") (pintype "passive"))
      (node (ref "C31") (pin "2") (pinfunction "2_2") (pintype "passive"))
      (node (ref "C33") (pin "1") (pinfunction "1_1") (pintype "passive"))
      (node (ref "C42") (pin "2") (pinfunction "2_2") (pintype "passive"))
      (node (ref "D2") (pin "1") (pinfunction "ANODE_1") (pintype "passive"))
      (node (ref "MC1") (pin "42") (pinfunction "VBAT_42") (pintype "passive"))
      (node (ref "MC1") (pin "43") (pinfunction "VBAT_43") (pintype "passive"))
      (node (ref "R7") (pin "2") (pinfunction "2_2") (pintype "passive"))
      (node (ref "TP4") (pin "1") (pinfunction "1_1") (pintype "passive"))
      (node (ref "U3") (pin "6") (pinfunction "OUT_6") (pintype "power_in"))
    )
    (net (code "73") (name "VDD_EXT") (class "Default")
      (node (ref "MC1") (pin "24") (pinfunction "VDD_EXT_24") (pintype "passive"))
      (node (ref "R18") (pin "2") (pinfunction "2_2") (pintype "passive"))
    )
    (net (code "74") (name "unconnected-(J3-VPP-PadC6)") (class "Default")
      (node (ref "J3") (pin "C6") (pinfunction "VPP_C6") (pintype "power_in+no_connect"))
    )
    (net (code "75") (name "unconnected-(MC1-ADC0-Pad9)") (class "Default")
      (node (ref "MC1") (pin "9") (pinfunction "ADC0_9") (pintype "passive+no_connect"))
    )
    (net (code "76") (name "unconnected-(MC1-AVDD-Pad8)") (class "Default")
      (node (ref "MC1") (pin "8") (pinfunction "AVDD_8") (pintype "passive+no_connect"))
    )
    (net (code "77") (name "unconnected-(MC1-BT_ANT-Pad26)") (class "Default")
      (node (ref "MC1") (pin "26") (pinfunction "BT_ANT_26") (pintype "passive+no_connect"))
    )
    (net (code "78") (name "unconnected-(MC1-CTS-Pad22)") (class "Default")
      (node (ref "MC1") (pin "22") (pinfunction "CTS_22") (pintype "passive+no_connect"))
    )
    (net (code "79") (name "unconnected-(MC1-DBG_RXD-Pad38)") (class "Default")
      (node (ref "MC1") (pin "38") (pinfunction "DBG_RXD_38") (pintype "passive+no_connect"))
    )
    (net (code "80") (name "unconnected-(MC1-DBG_TXD-Pad39)") (class "Default")
      (node (ref "MC1") (pin "39") (pinfunction "DBG_TXD_39") (pintype "passive+no_connect"))
    )
    (net (code "81") (name "unconnected-(MC1-DCD-Pad21)") (class "Default")
      (node (ref "MC1") (pin "21") (pinfunction "DCD_21") (pintype "passive+no_connect"))
    )
    (net (code "82") (name "unconnected-(MC1-DTR-Pad19)") (class "Default")
      (node (ref "MC1") (pin "19") (pinfunction "DTR_19") (pintype "passive+no_connect"))
    )
    (net (code "83") (name "unconnected-(MC1-MICN-Pad4)") (class "Default")
      (node (ref "MC1") (pin "4") (pinfunction "MICN_4") (pintype "passive+no_connect"))
    )
    (net (code "84") (name "unconnected-(MC1-MICP-Pad3)") (class "Default")
      (node (ref "MC1") (pin "3") (pinfunction "MICP_3") (pintype "passive+no_connect"))
    )
    (net (code "85") (name "unconnected-(MC1-PCM_CLK-Pad30)") (class "Default")
      (node (ref "MC1") (pin "30") (pinfunction "PCM_CLK_30") (pintype "passive+no_connect"))
    )
    (net (code "86") (name "unconnected-(MC1-PCM_IN-Pad32)") (class "Default")
      (node (ref "MC1") (pin "32") (pinfunction "PCM_IN_32") (pintype "passive+no_connect"))
    )
    (net (code "87") (name "unconnected-(MC1-PCM_OUT-Pad33)") (class "Default")
      (node (ref "MC1") (pin "33") (pinfunction "PCM_OUT_33") (pintype "passive+no_connect"))
    )
    (net (code "88") (name "unconnected-(MC1-PCM_SYNC-Pad31)") (class "Default")
      (node (ref "MC1") (pin "31") (pinfunction "PCM_SYNC_31") (pintype "passive+no_connect"))
    )
    (net (code "89") (name "unconnected-(MC1-RFTXMON-Pad25)") (class "Default")
      (node (ref "MC1") (pin "25") (pinfunction "RFTXMON_25") (pintype "passive+no_connect"))
    )
    (net (code "90") (name "unconnected-(MC1-RI-Pad20)") (class "Default")
      (node (ref "MC1") (pin "20") (pinfunction "RI_20") (pintype "passive+no_connect"))
    )
    (net (code "91") (name "unconnected-(MC1-RTS-Pad23)") (class "Default")
      (node (ref "MC1") (pin "23") (pinfunction "RTS_23") (pintype "passive+no_connect"))
    )
    (net (code "92") (name "unconnected-(MC1-RXD_AUX-Pad28)") (class "Default")
      (node (ref "MC1") (pin "28") (pinfunction "RXD_AUX_28") (pintype "passive+no_connect"))
    )
    (net (code "93") (name "unconnected-(MC1-SPK1N-Pad6)") (class "Default")
      (node (ref "MC1") (pin "6") (pinfunction "SPK1N_6") (pintype "passive+no_connect"))
    )
    (net (code "94") (name "unconnected-(MC1-SPK1P-Pad5)") (class "Default")
      (node (ref "MC1") (pin "5") (pinfunction "SPK1P_5") (pintype "passive+no_connect"))
    )
    (net (code "95") (name "unconnected-(MC1-SPK2P-Pad2)") (class "Default")
      (node (ref "MC1") (pin "2") (pinfunction "SPK2P_2") (pintype "passive+no_connect"))
    )
    (net (code "96") (name "unconnected-(MC1-TXD_AUX-Pad29)") (class "Default")
      (node (ref "MC1") (pin "29") (pinfunction "TXD_AUX_29") (pintype "passive+no_connect"))
    )
    (net (code "97") (name "unconnected-(MC1-VRTC-Pad44)") (class "Default")
      (node (ref "MC1") (pin "44") (pinfunction "VRTC_44") (pintype "passive+no_connect"))
    )
    (net (code "98") (name "unconnected-(U2-PA0-Pad11)") (class "Default")
      (node (ref "U2") (pin "11") (pinfunction "PA0_11") (pintype "bidirectional+no_connect"))
    )
    (net (code "99") (name "unconnected-(U2-PA1-Pad12)") (class "Default")
      (node (ref "U2") (pin "12") (pinfunction "PA1_12") (pintype "bidirectional+no_connect"))
    )
    (net (code "100") (name "unconnected-(U2-PB1-Pad20)") (class "Default")
      (node (ref "U2") (pin "20") (pinfunction "PB1_20") (pintype "bidirectional+no_connect"))
    )
    (net (code "101") (name "unconnected-(U2-PB2-Pad21)") (class "Default")
      (node (ref "U2") (pin "21") (pinfunction "PB2_21") (pintype "bidirectional+no_connect"))
    )
    (net (code "102") (name "unconnected-(U2-PB3-Pad42)") (class "Default")
      (node (ref "U2") (pin "42") (pinfunction "PB3_42") (pintype "bidirectional+no_connect"))
    )
    (net (code "103") (name "unconnected-(U2-PB4-Pad43)") (class "Default")
      (node (ref "U2") (pin "43") (pinfunction "PB4_43") (pintype "bidirectional+no_connect"))
    )
    (net (code "104") (name "unconnected-(U2-PB5-Pad44)") (class "Default")
      (node (ref "U2") (pin "44") (pinfunction "PB5_44") (pintype "bidirectional+no_connect"))
    )
    (net (code "105") (name "unconnected-(U2-PB6-Pad45)") (class "Default")
      (node (ref "U2") (pin "45") (pinfunction "PB6_45") (pintype "bidirectional+no_connect"))
    )
    (net (code "106") (name "unconnected-(U2-PB7-Pad46)") (class "Default")
      (node (ref "U2") (pin "46") (pinfunction "PB7_46") (pintype "bidirectional+no_connect"))
    )
    (net (code "107") (name "unconnected-(U2-PB9-Pad48)") (class "Default")
      (node (ref "U2") (pin "48") (pinfunction "PB9_48") (pintype "bidirectional+no_connect"))
    )
    (net (code "108") (name "unconnected-(U2-PB10-Pad22)") (class "Default")
      (node (ref "U2") (pin "22") (pinfunction "PB10_22") (pintype "bidirectional+no_connect"))
    )
    (net (code "109") (name "unconnected-(U2-PB11-Pad23)") (class "Default")
      (node (ref "U2") (pin "23") (pinfunction "PB11_23") (pintype "bidirectional+no_connect"))
    )
    (net (code "110") (name "unconnected-(U2-PB12-Pad24)") (class "Default")
      (node (ref "U2") (pin "24") (pinfunction "PB12_24") (pintype "bidirectional+no_connect"))
    )
    (net (code "111") (name "unconnected-(U2-PC13-Pad1)") (class "Default")
      (node (ref "U2") (pin "1") (pinfunction "PC13_1") (pintype "bidirectional+no_connect"))
    )
    (net (code "112") (name "unconnected-(U2-PC14-OSC32_IN-Pad2)") (class "Default")
      (node (ref "U2") (pin "2") (pinfunction "PC14-OSC32_IN_2") (pintype "bidirectional+no_connect"))
    )
    (net (code "113") (name "unconnected-(U2-PC15-OSC32_OUT-Pad3)") (class "Default")
      (node (ref "U2") (pin "3") (pinfunction "PC15-OSC32_OUT_3") (pintype "bidirectional+no_connect"))
    )
    (net (code "114") (name "unconnected-(U2-PD0-Pad38)") (class "Default")
      (node (ref "U2") (pin "38") (pinfunction "PD0_38") (pintype "bidirectional+no_connect"))
    )
    (net (code "115") (name "unconnected-(U2-PD1-Pad39)") (class "Default")
      (node (ref "U2") (pin "39") (pinfunction "PD1_39") (pintype "bidirectional+no_connect"))
    )
    (net (code "116") (name "unconnected-(U2-PD2-Pad40)") (class "Default")
      (node (ref "U2") (pin "40") (pinfunction "PD2_40") (pintype "bidirectional+no_connect"))
    )
    (net (code "117") (name "unconnected-(U2-PD3-Pad41)") (class "Default")
      (node (ref "U2") (pin "41") (pinfunction "PD3_41") (pintype "bidirectional+no_connect"))
    )
    (net (code "118") (name "unconnected-(U3-NC_1-Pad1)") (class "Default")
      (node (ref "U3") (pin "1") (pinfunction "NC_1_1") (pintype "passive+no_connect"))
    )
    (net (code "119") (name "unconnected-(U3-NC_4-Pad4)") (class "Default")
      (node (ref "U3") (pin "4") (pinfunction "NC_4_4") (pintype "passive+no_connect"))
    )
    (net (code "120") (name "unconnected-(U3-NC_5-Pad5)") (class "Default")
      (node (ref "U3") (pin "5") (pinfunction "NC_5_5") (pintype "passive+no_connect"))
    )
    (net (code "121") (name "unconnected-(U5-C3-Pad4)") (class "Default")
      (node (ref "U5") (pin "4") (pinfunction "C3_4") (pintype "passive+no_connect"))
    )
  )
)
